# I2C-Oled-Backpack-EastRising.net
KiCad netlist of a schematic drawn in EAGLE
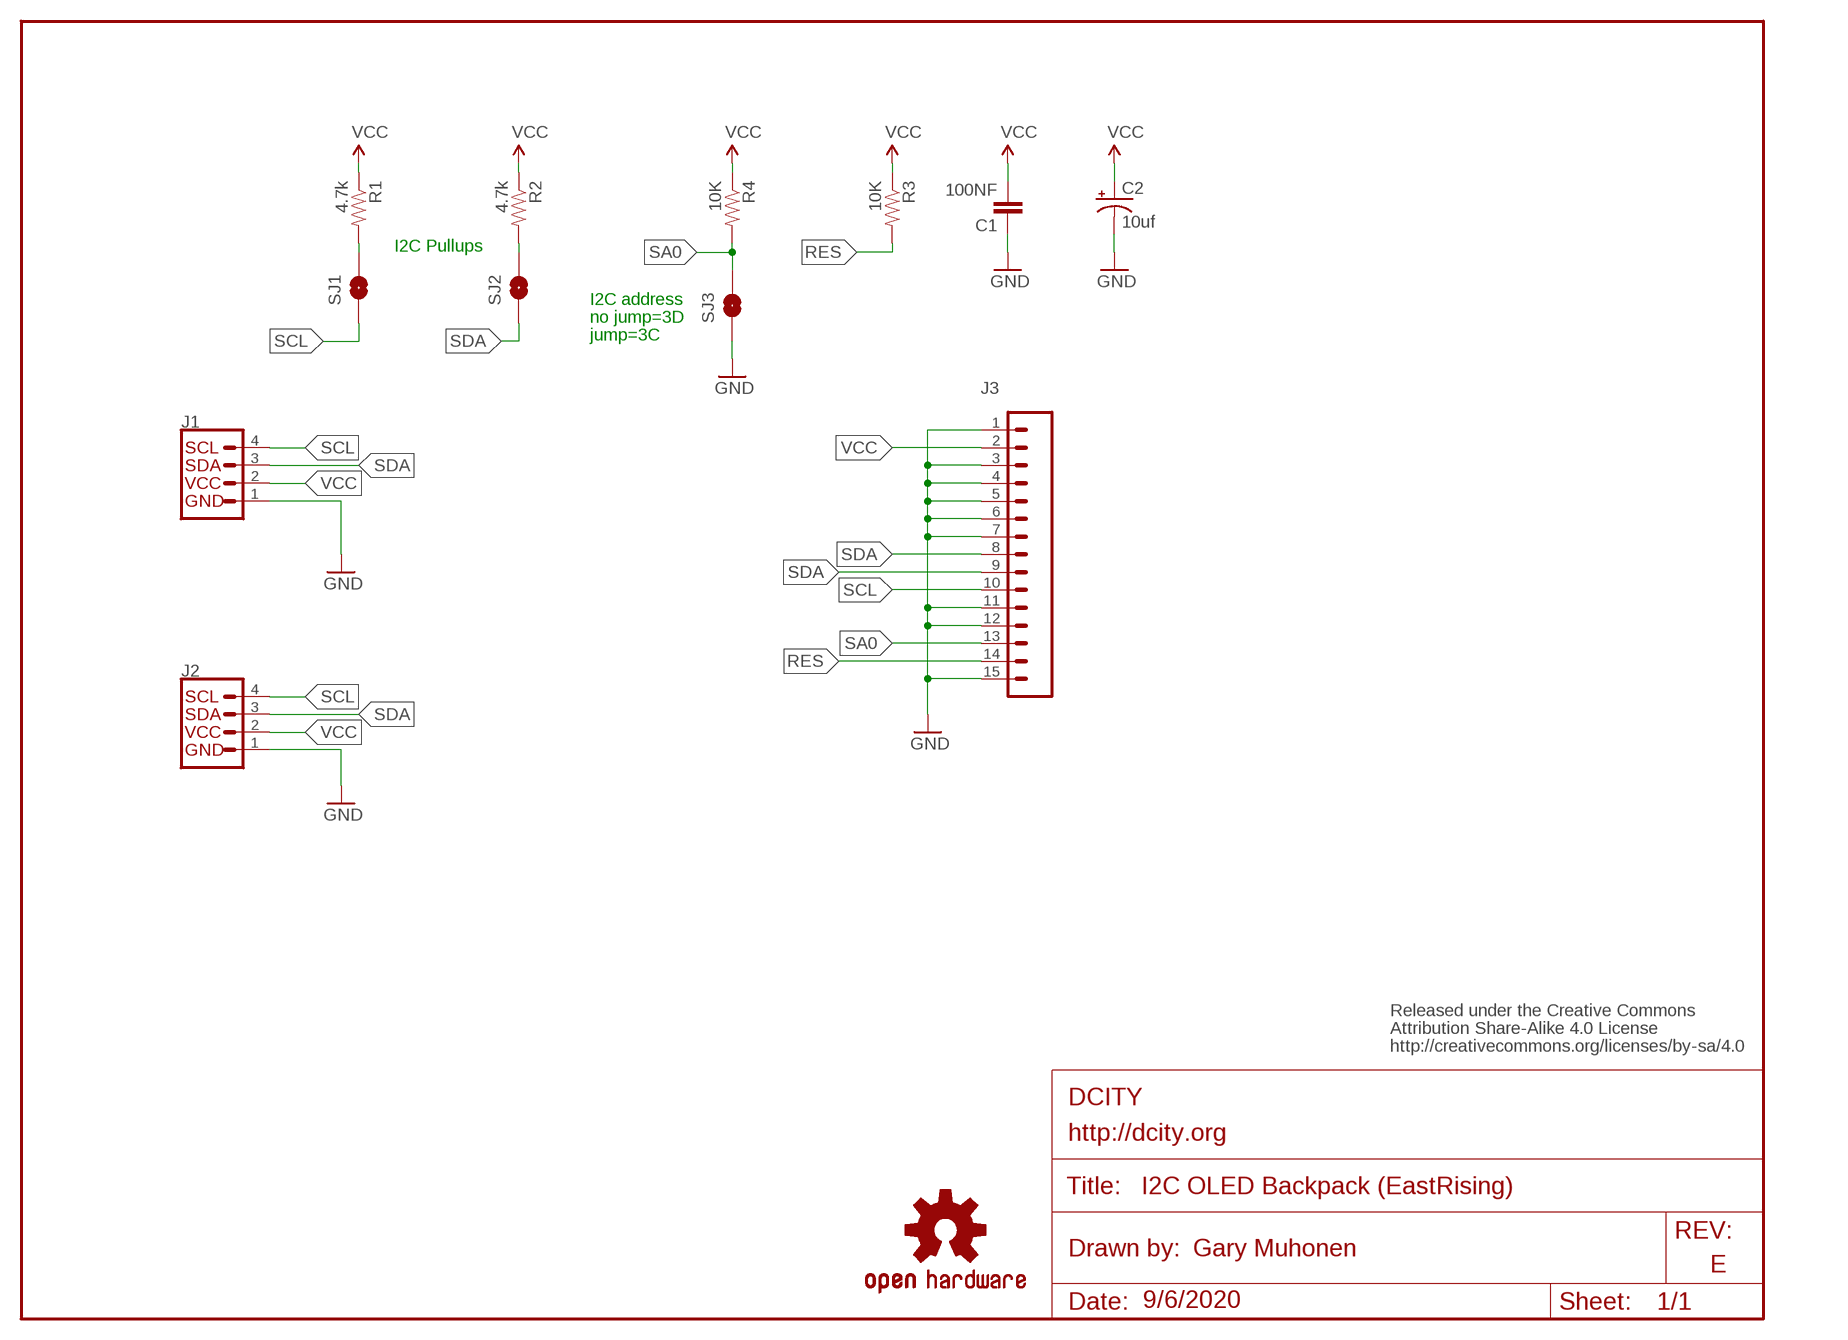
[diagram p0: schematic, sheet 1]

(export (version "E")
  (design (tool "Eeschema 10.0.6"))
  (components
    (comp (ref "C1")
      (value "100NF")
      (footprint "eagle-import:0805-CAP")
      (libsource (lib "eagle-import") (part "CAP0805"))
    )
    (comp (ref "C2")
      (value "10uf")
      (footprint "eagle-import:0805-POL")
      (libsource (lib "eagle-import") (part "CAP_POL0805"))
    )
    (comp (ref "J1")
      (value "QWIIC_RIGHT_ANGLE")
      (footprint "eagle-import:JST04_1MM_RA")
      (libsource (lib "eagle-import") (part "QWIIC_CONNECTORJS-1MM"))
    )
    (comp (ref "J2")
      (value "QWIIC_RIGHT_ANGLE")
      (footprint "eagle-import:JST04_1MM_RA")
      (libsource (lib "eagle-import") (part "QWIIC_CONNECTORJS-1MM"))
    )
    (comp (ref "J3")
      (value "15P-2.54")
      (footprint "eagle-import:1X15_LOCK")
      (libsource (lib "eagle-import") (part "M15LOCK"))
    )
    (comp (ref "LOGO1")
      (value "OSHW-LOGOS")
      (footprint "eagle-import:OSHW-LOGO-S")
      (libsource (lib "eagle-import") (part "OSHW-LOGOS"))
    )
    (comp (ref "R1")
      (value "4.7k")
      (footprint "eagle-import:0805-RES")
      (libsource (lib "eagle-import") (part "RESISTOR0805"))
    )
    (comp (ref "R2")
      (value "4.7k")
      (footprint "eagle-import:0805-RES")
      (libsource (lib "eagle-import") (part "RESISTOR0805"))
    )
    (comp (ref "R3")
      (value "10K")
      (footprint "eagle-import:0805-RES")
      (libsource (lib "eagle-import") (part "RESISTOR0805"))
    )
    (comp (ref "R4")
      (value "10K")
      (footprint "eagle-import:0805-RES")
      (libsource (lib "eagle-import") (part "RESISTOR0805"))
    )
    (comp (ref "SJ1")
      (value "SOLDERJUMPERNC")
      (footprint "eagle-import:SJ_2S")
      (libsource (lib "eagle-import") (part "SOLDERJUMPERNC"))
    )
    (comp (ref "SJ2")
      (value "SOLDERJUMPERNC")
      (footprint "eagle-import:SJ_2S")
      (libsource (lib "eagle-import") (part "SOLDERJUMPERNC"))
    )
    (comp (ref "SJ3")
      (value "SOLDERJUMPERNC")
      (footprint "eagle-import:SJ_2S")
      (libsource (lib "eagle-import") (part "SOLDERJUMPERNC"))
    )
    (comp (ref "U$2")
      (value "CREATIVE_COMMONS")
      (footprint "eagle-import:CREATIVE_COMMONS")
      (libsource (lib "eagle-import") (part "CREATIVE_COMMONS"))
    )
  )
  (nets
    (net (code "1") (name "GND") (class "Default")
      (node (ref "C1") (pin "1") (pinfunction "1_1") (pintype "passive"))
      (node (ref "C2") (pin "-") (pinfunction "-_-") (pintype "passive"))
      (node (ref "J1") (pin "1") (pinfunction "1_1") (pintype "power_in"))
      (node (ref "J2") (pin "1") (pinfunction "1_1") (pintype "power_in"))
      (node (ref "J3") (pin "1") (pinfunction "1_1") (pintype "passive"))
      (node (ref "J3") (pin "11") (pinfunction "11_11") (pintype "passive"))
      (node (ref "J3") (pin "12") (pinfunction "12_12") (pintype "passive"))
      (node (ref "J3") (pin "15") (pinfunction "15_15") (pintype "passive"))
      (node (ref "J3") (pin "3") (pinfunction "3_3") (pintype "passive"))
      (node (ref "J3") (pin "4") (pinfunction "4_4") (pintype "passive"))
      (node (ref "J3") (pin "5") (pinfunction "5_5") (pintype "passive"))
      (node (ref "J3") (pin "6") (pinfunction "6_6") (pintype "passive"))
      (node (ref "J3") (pin "7") (pinfunction "7_7") (pintype "passive"))
      (node (ref "SJ3") (pin "1") (pinfunction "1_1") (pintype "passive"))
    )
    (net (code "2") (name "Net-(R1-Pad2)") (class "Default")
      (node (ref "R1") (pin "2") (pinfunction "2_2") (pintype "passive"))
      (node (ref "SJ1") (pin "2") (pinfunction "2_2") (pintype "passive"))
    )
    (net (code "3") (name "Net-(R2-Pad2)") (class "Default")
      (node (ref "R2") (pin "2") (pinfunction "2_2") (pintype "passive"))
      (node (ref "SJ2") (pin "2") (pinfunction "2_2") (pintype "passive"))
    )
    (net (code "4") (name "RES") (class "Default")
      (node (ref "J3") (pin "14") (pinfunction "14_14") (pintype "passive"))
      (node (ref "R3") (pin "2") (pinfunction "2_2") (pintype "passive"))
    )
    (net (code "5") (name "SA0") (class "Default")
      (node (ref "J3") (pin "13") (pinfunction "13_13") (pintype "passive"))
      (node (ref "R4") (pin "2") (pinfunction "2_2") (pintype "passive"))
      (node (ref "SJ3") (pin "2") (pinfunction "2_2") (pintype "passive"))
    )
    (net (code "6") (name "SCL") (class "Default")
      (node (ref "J1") (pin "4") (pinfunction "4_4") (pintype "passive"))
      (node (ref "J2") (pin "4") (pinfunction "4_4") (pintype "passive"))
      (node (ref "J3") (pin "10") (pinfunction "10_10") (pintype "passive"))
      (node (ref "SJ1") (pin "1") (pinfunction "1_1") (pintype "passive"))
    )
    (net (code "7") (name "SDA") (class "Default")
      (node (ref "J1") (pin "3") (pinfunction "3_3") (pintype "passive"))
      (node (ref "J2") (pin "3") (pinfunction "3_3") (pintype "passive"))
      (node (ref "J3") (pin "8") (pinfunction "8_8") (pintype "passive"))
      (node (ref "J3") (pin "9") (pinfunction "9_9") (pintype "passive"))
      (node (ref "SJ2") (pin "1") (pinfunction "1_1") (pintype "passive"))
    )
    (net (code "8") (name "VCC") (class "Default")
      (node (ref "C1") (pin "2") (pinfunction "2_2") (pintype "passive"))
      (node (ref "C2") (pin "+") (pinfunction "+_+") (pintype "passive"))
      (node (ref "J1") (pin "2") (pinfunction "2_2") (pintype "power_in"))
      (node (ref "J2") (pin "2") (pinfunction "2_2") (pintype "power_in"))
      (node (ref "J3") (pin "2") (pinfunction "2_2") (pintype "passive"))
      (node (ref "R1") (pin "1") (pinfunction "1_1") (pintype "passive"))
      (node (ref "R2") (pin "1") (pinfunction "1_1") (pintype "passive"))
      (node (ref "R3") (pin "1") (pinfunction "1_1") (pintype "passive"))
      (node (ref "R4") (pin "1") (pinfunction "1_1") (pintype "passive"))
    )
  )
)
